# R613X.net
KiCad netlist of a schematic drawn in EAGLE
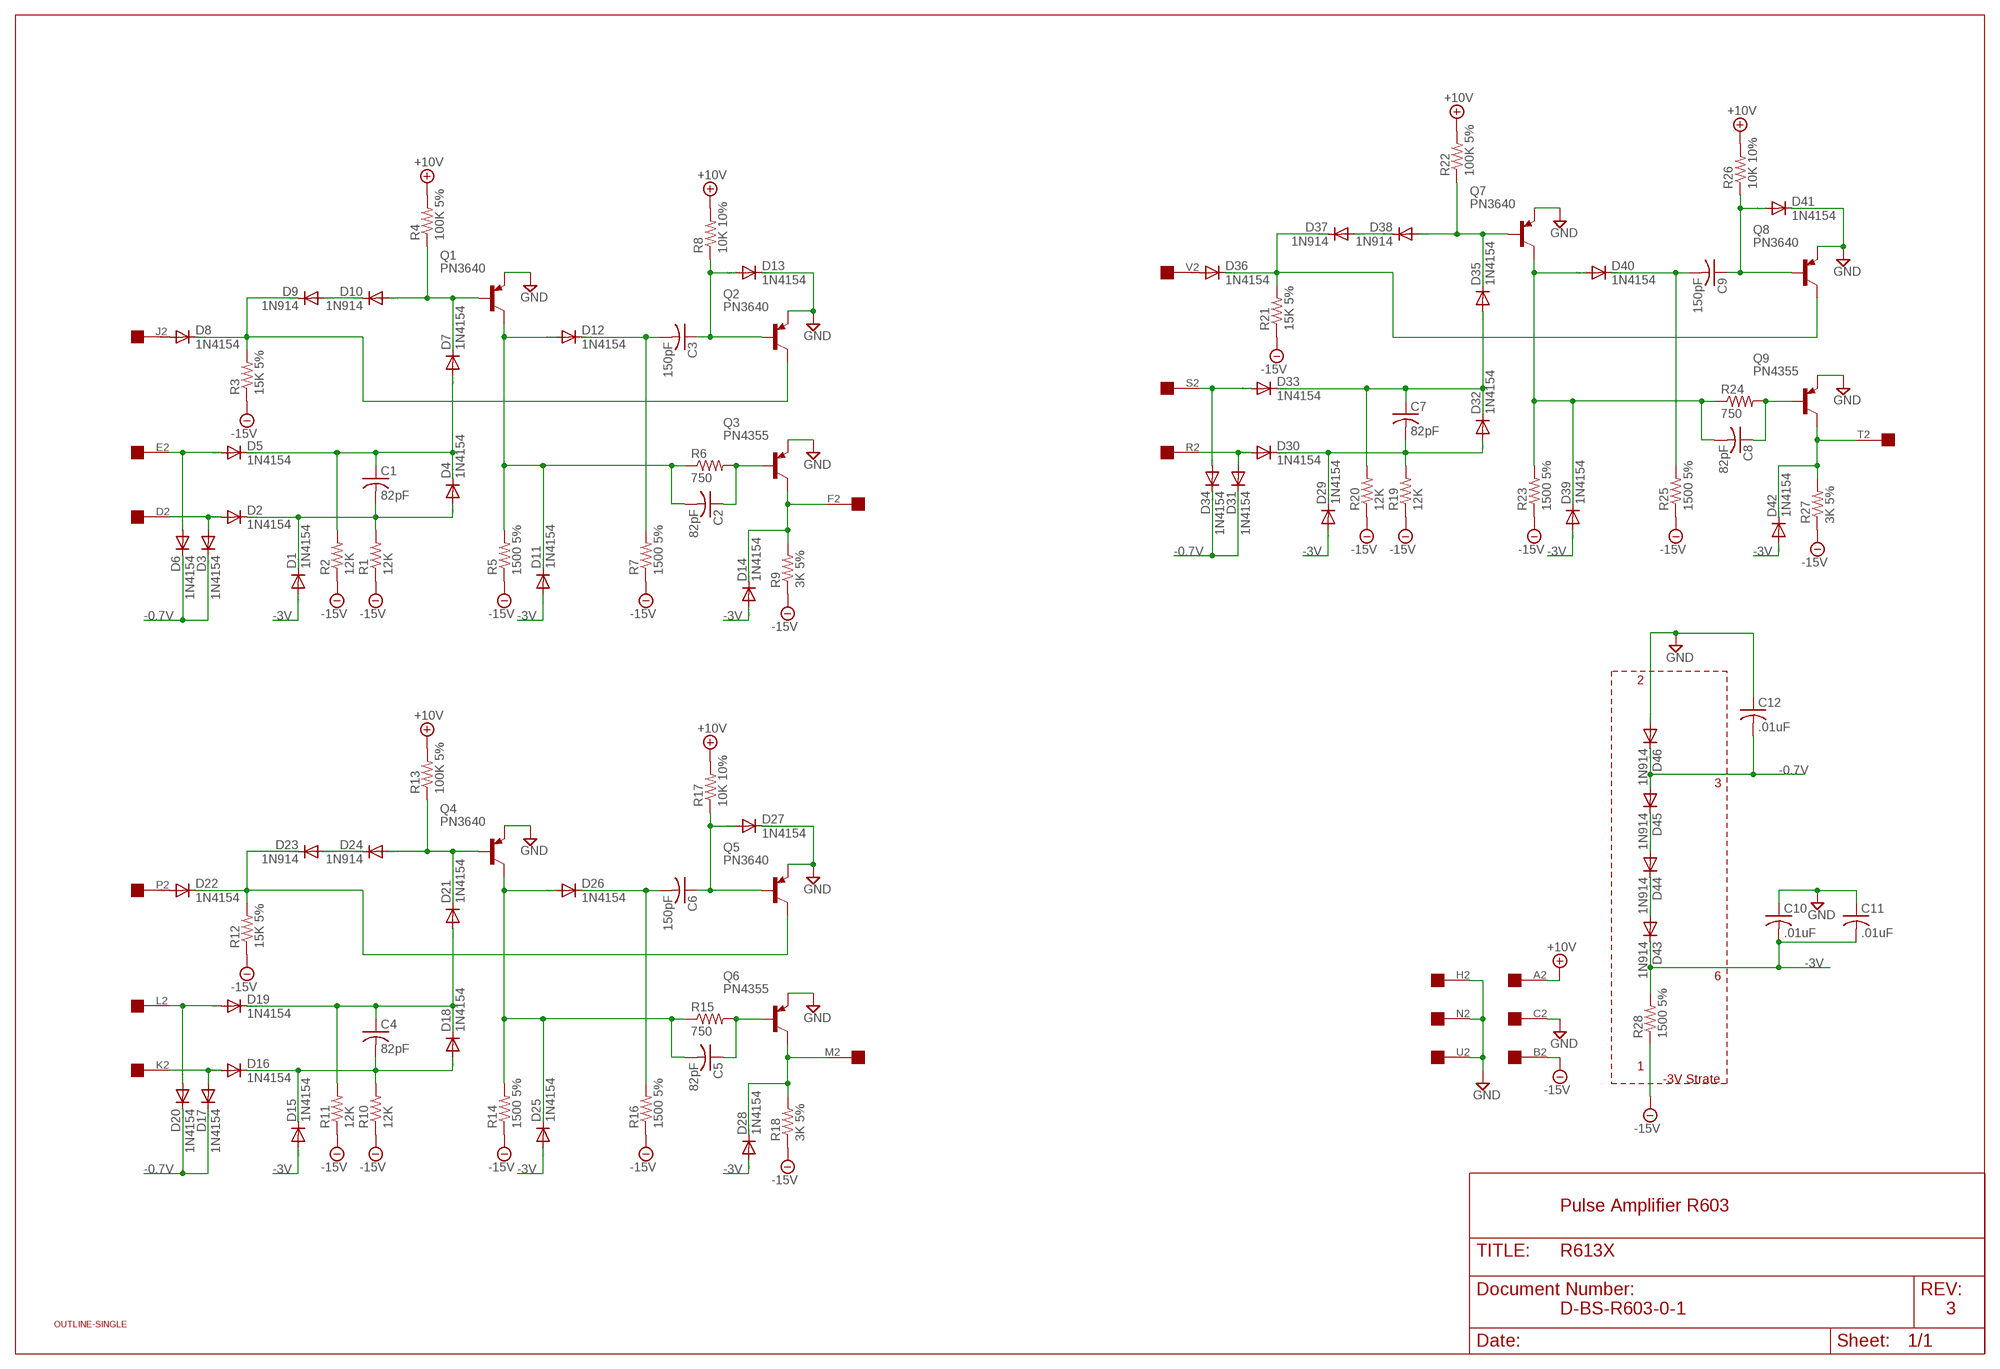
[diagram p0: schematic, sheet 1]

(export (version "E")
  (design (tool "Eeschema 10.0.6"))
  (components
    (comp (ref "C1")
      (value "82pF")
      (footprint "eagle-import:C050-025X075")
      (libsource (lib "eagle-import") (part "C-US050-025X075"))
    )
    (comp (ref "C2")
      (value "82pF")
      (footprint "eagle-import:C050-025X075")
      (libsource (lib "eagle-import") (part "C-US050-025X075"))
    )
    (comp (ref "C3")
      (value "150pF")
      (footprint "eagle-import:C050-025X075")
      (libsource (lib "eagle-import") (part "C-US050-025X075"))
    )
    (comp (ref "C4")
      (value "82pF")
      (footprint "eagle-import:C050-025X075")
      (libsource (lib "eagle-import") (part "C-US050-025X075"))
    )
    (comp (ref "C5")
      (value "82pF")
      (footprint "eagle-import:C050-025X075")
      (libsource (lib "eagle-import") (part "C-US050-025X075"))
    )
    (comp (ref "C6")
      (value "150pF")
      (footprint "eagle-import:C050-025X075")
      (libsource (lib "eagle-import") (part "C-US050-025X075"))
    )
    (comp (ref "C7")
      (value "82pF")
      (footprint "eagle-import:C050-025X075")
      (libsource (lib "eagle-import") (part "C-US050-025X075"))
    )
    (comp (ref "C8")
      (value "82pF")
      (footprint "eagle-import:C050-025X075")
      (libsource (lib "eagle-import") (part "C-US050-025X075"))
    )
    (comp (ref "C9")
      (value "150pF")
      (footprint "eagle-import:C050-025X075")
      (libsource (lib "eagle-import") (part "C-US050-025X075"))
    )
    (comp (ref "C10")
      (value ".01uF")
      (footprint "eagle-import:C050-025X075")
      (libsource (lib "eagle-import") (part "C-US050-025X075"))
    )
    (comp (ref "C11")
      (value ".01uF")
      (footprint "eagle-import:C050-025X075")
      (libsource (lib "eagle-import") (part "C-US050-025X075"))
    )
    (comp (ref "C12")
      (value ".01uF")
      (footprint "eagle-import:C050-025X075")
      (libsource (lib "eagle-import") (part "C-US050-025X075"))
    )
    (comp (ref "D1")
      (value "1N4154")
      (footprint "eagle-import:DO35-10")
      (libsource (lib "eagle-import") (part "1N4148DO35-10"))
    )
    (comp (ref "D2")
      (value "1N4154")
      (footprint "eagle-import:DO35-10")
      (libsource (lib "eagle-import") (part "1N4148DO35-10"))
    )
    (comp (ref "D3")
      (value "1N4154")
      (footprint "eagle-import:DO35-10")
      (libsource (lib "eagle-import") (part "1N4148DO35-10"))
    )
    (comp (ref "D4")
      (value "1N4154")
      (footprint "eagle-import:DO35-10")
      (libsource (lib "eagle-import") (part "1N4148DO35-10"))
    )
    (comp (ref "D5")
      (value "1N4154")
      (footprint "eagle-import:DO35-10")
      (libsource (lib "eagle-import") (part "1N4148DO35-10"))
    )
    (comp (ref "D6")
      (value "1N4154")
      (footprint "eagle-import:DO35-10")
      (libsource (lib "eagle-import") (part "1N4148DO35-10"))
    )
    (comp (ref "D7")
      (value "1N4154")
      (footprint "eagle-import:DO35-10")
      (libsource (lib "eagle-import") (part "1N4148DO35-10"))
    )
    (comp (ref "D8")
      (value "1N4154")
      (footprint "eagle-import:DO35-10")
      (libsource (lib "eagle-import") (part "1N4148DO35-10"))
    )
    (comp (ref "D9")
      (value "1N914")
      (footprint "eagle-import:DO35-10")
      (libsource (lib "eagle-import") (part "1N4148DO35-10"))
    )
    (comp (ref "D10")
      (value "1N914")
      (footprint "eagle-import:DO35-10")
      (libsource (lib "eagle-import") (part "1N4148DO35-10"))
    )
    (comp (ref "D11")
      (value "1N4154")
      (footprint "eagle-import:DO35-10")
      (libsource (lib "eagle-import") (part "1N4148DO35-10"))
    )
    (comp (ref "D12")
      (value "1N4154")
      (footprint "eagle-import:DO35-10")
      (libsource (lib "eagle-import") (part "1N4148DO35-10"))
    )
    (comp (ref "D13")
      (value "1N4154")
      (footprint "eagle-import:DO35-10")
      (libsource (lib "eagle-import") (part "1N4148DO35-10"))
    )
    (comp (ref "D14")
      (value "1N4154")
      (footprint "eagle-import:DO35-10")
      (libsource (lib "eagle-import") (part "1N4148DO35-10"))
    )
    (comp (ref "D15")
      (value "1N4154")
      (footprint "eagle-import:DO35-10")
      (libsource (lib "eagle-import") (part "1N4148DO35-10"))
    )
    (comp (ref "D16")
      (value "1N4154")
      (footprint "eagle-import:DO35-10")
      (libsource (lib "eagle-import") (part "1N4148DO35-10"))
    )
    (comp (ref "D17")
      (value "1N4154")
      (footprint "eagle-import:DO35-10")
      (libsource (lib "eagle-import") (part "1N4148DO35-10"))
    )
    (comp (ref "D18")
      (value "1N4154")
      (footprint "eagle-import:DO35-10")
      (libsource (lib "eagle-import") (part "1N4148DO35-10"))
    )
    (comp (ref "D19")
      (value "1N4154")
      (footprint "eagle-import:DO35-10")
      (libsource (lib "eagle-import") (part "1N4148DO35-10"))
    )
    (comp (ref "D20")
      (value "1N4154")
      (footprint "eagle-import:DO35-10")
      (libsource (lib "eagle-import") (part "1N4148DO35-10"))
    )
    (comp (ref "D21")
      (value "1N4154")
      (footprint "eagle-import:DO35-10")
      (libsource (lib "eagle-import") (part "1N4148DO35-10"))
    )
    (comp (ref "D22")
      (value "1N4154")
      (footprint "eagle-import:DO35-10")
      (libsource (lib "eagle-import") (part "1N4148DO35-10"))
    )
    (comp (ref "D23")
      (value "1N914")
      (footprint "eagle-import:DO35-10")
      (libsource (lib "eagle-import") (part "1N4148DO35-10"))
    )
    (comp (ref "D24")
      (value "1N914")
      (footprint "eagle-import:DO35-10")
      (libsource (lib "eagle-import") (part "1N4148DO35-10"))
    )
    (comp (ref "D25")
      (value "1N4154")
      (footprint "eagle-import:DO35-10")
      (libsource (lib "eagle-import") (part "1N4148DO35-10"))
    )
    (comp (ref "D26")
      (value "1N4154")
      (footprint "eagle-import:DO35-10")
      (libsource (lib "eagle-import") (part "1N4148DO35-10"))
    )
    (comp (ref "D27")
      (value "1N4154")
      (footprint "eagle-import:DO35-10")
      (libsource (lib "eagle-import") (part "1N4148DO35-10"))
    )
    (comp (ref "D28")
      (value "1N4154")
      (footprint "eagle-import:DO35-10")
      (libsource (lib "eagle-import") (part "1N4148DO35-10"))
    )
    (comp (ref "D29")
      (value "1N4154")
      (footprint "eagle-import:DO35-10")
      (libsource (lib "eagle-import") (part "1N4148DO35-10"))
    )
    (comp (ref "D30")
      (value "1N4154")
      (footprint "eagle-import:DO35-10")
      (libsource (lib "eagle-import") (part "1N4148DO35-10"))
    )
    (comp (ref "D31")
      (value "1N4154")
      (footprint "eagle-import:DO35-10")
      (libsource (lib "eagle-import") (part "1N4148DO35-10"))
    )
    (comp (ref "D32")
      (value "1N4154")
      (footprint "eagle-import:DO35-10")
      (libsource (lib "eagle-import") (part "1N4148DO35-10"))
    )
    (comp (ref "D33")
      (value "1N4154")
      (footprint "eagle-import:DO35-10")
      (libsource (lib "eagle-import") (part "1N4148DO35-10"))
    )
    (comp (ref "D34")
      (value "1N4154")
      (footprint "eagle-import:DO35-10")
      (libsource (lib "eagle-import") (part "1N4148DO35-10"))
    )
    (comp (ref "D35")
      (value "1N4154")
      (footprint "eagle-import:DO35-10")
      (libsource (lib "eagle-import") (part "1N4148DO35-10"))
    )
    (comp (ref "D36")
      (value "1N4154")
      (footprint "eagle-import:DO35-10")
      (libsource (lib "eagle-import") (part "1N4148DO35-10"))
    )
    (comp (ref "D37")
      (value "1N914")
      (footprint "eagle-import:DO35-10")
      (libsource (lib "eagle-import") (part "1N4148DO35-10"))
    )
    (comp (ref "D38")
      (value "1N914")
      (footprint "eagle-import:DO35-10")
      (libsource (lib "eagle-import") (part "1N4148DO35-10"))
    )
    (comp (ref "D39")
      (value "1N4154")
      (footprint "eagle-import:DO35-10")
      (libsource (lib "eagle-import") (part "1N4148DO35-10"))
    )
    (comp (ref "D40")
      (value "1N4154")
      (footprint "eagle-import:DO35-10")
      (libsource (lib "eagle-import") (part "1N4148DO35-10"))
    )
    (comp (ref "D41")
      (value "1N4154")
      (footprint "eagle-import:DO35-10")
      (libsource (lib "eagle-import") (part "1N4148DO35-10"))
    )
    (comp (ref "D42")
      (value "1N4154")
      (footprint "eagle-import:DO35-10")
      (libsource (lib "eagle-import") (part "1N4148DO35-10"))
    )
    (comp (ref "D43")
      (value "1N914")
      (footprint "eagle-import:DO35-10")
      (libsource (lib "eagle-import") (part "1N4148DO35-10"))
    )
    (comp (ref "D44")
      (value "1N914")
      (footprint "eagle-import:DO35-10")
      (libsource (lib "eagle-import") (part "1N4148DO35-10"))
    )
    (comp (ref "D45")
      (value "1N914")
      (footprint "eagle-import:DO35-10")
      (libsource (lib "eagle-import") (part "1N4148DO35-10"))
    )
    (comp (ref "D46")
      (value "1N914")
      (footprint "eagle-import:DO35-10")
      (libsource (lib "eagle-import") (part "1N4148DO35-10"))
    )
    (comp (ref "Q1")
      (value "PN3640")
      (footprint "eagle-import:TO39")
      (libsource (lib "eagle-import") (part "2N2904"))
    )
    (comp (ref "Q2")
      (value "PN3640")
      (footprint "eagle-import:TO39")
      (libsource (lib "eagle-import") (part "2N2904"))
    )
    (comp (ref "Q3")
      (value "PN4355")
      (footprint "eagle-import:TO39")
      (libsource (lib "eagle-import") (part "2N2904"))
    )
    (comp (ref "Q4")
      (value "PN3640")
      (footprint "eagle-import:TO39")
      (libsource (lib "eagle-import") (part "2N2904"))
    )
    (comp (ref "Q5")
      (value "PN3640")
      (footprint "eagle-import:TO39")
      (libsource (lib "eagle-import") (part "2N2904"))
    )
    (comp (ref "Q6")
      (value "PN4355")
      (footprint "eagle-import:TO39")
      (libsource (lib "eagle-import") (part "2N2904"))
    )
    (comp (ref "Q7")
      (value "PN3640")
      (footprint "eagle-import:TO39")
      (libsource (lib "eagle-import") (part "2N2904"))
    )
    (comp (ref "Q8")
      (value "PN3640")
      (footprint "eagle-import:TO39")
      (libsource (lib "eagle-import") (part "2N2904"))
    )
    (comp (ref "Q9")
      (value "PN4355")
      (footprint "eagle-import:TO39")
      (libsource (lib "eagle-import") (part "2N2904"))
    )
    (comp (ref "R1")
      (value "12K")
      (footprint "eagle-import:0207_10")
      (libsource (lib "eagle-import") (part "R-US_0207/10"))
    )
    (comp (ref "R2")
      (value "12K")
      (footprint "eagle-import:0207_10")
      (libsource (lib "eagle-import") (part "R-US_0207/10"))
    )
    (comp (ref "R3")
      (value "15K 5%")
      (footprint "eagle-import:0207_10")
      (libsource (lib "eagle-import") (part "R-US_0207/10"))
    )
    (comp (ref "R4")
      (value "100K 5%")
      (footprint "eagle-import:0207_10")
      (libsource (lib "eagle-import") (part "R-US_0207/10"))
    )
    (comp (ref "R5")
      (value "1500 5%")
      (footprint "eagle-import:0207_10")
      (libsource (lib "eagle-import") (part "R-US_0207/10"))
    )
    (comp (ref "R6")
      (value "750")
      (footprint "eagle-import:0207_10")
      (libsource (lib "eagle-import") (part "R-US_0207/10"))
    )
    (comp (ref "R7")
      (value "1500 5%")
      (footprint "eagle-import:0207_10")
      (libsource (lib "eagle-import") (part "R-US_0207/10"))
    )
    (comp (ref "R8")
      (value "10K 10%")
      (footprint "eagle-import:0207_10")
      (libsource (lib "eagle-import") (part "R-US_0207/10"))
    )
    (comp (ref "R9")
      (value "3K 5%")
      (footprint "eagle-import:0207_10")
      (libsource (lib "eagle-import") (part "R-US_0207/10"))
    )
    (comp (ref "R10")
      (value "12K")
      (footprint "eagle-import:0207_10")
      (libsource (lib "eagle-import") (part "R-US_0207/10"))
    )
    (comp (ref "R11")
      (value "12K")
      (footprint "eagle-import:0207_10")
      (libsource (lib "eagle-import") (part "R-US_0207/10"))
    )
    (comp (ref "R12")
      (value "15K 5%")
      (footprint "eagle-import:0207_10")
      (libsource (lib "eagle-import") (part "R-US_0207/10"))
    )
    (comp (ref "R13")
      (value "100K 5%")
      (footprint "eagle-import:0207_10")
      (libsource (lib "eagle-import") (part "R-US_0207/10"))
    )
    (comp (ref "R14")
      (value "1500 5%")
      (footprint "eagle-import:0207_10")
      (libsource (lib "eagle-import") (part "R-US_0207/10"))
    )
    (comp (ref "R15")
      (value "750")
      (footprint "eagle-import:0207_10")
      (libsource (lib "eagle-import") (part "R-US_0207/10"))
    )
    (comp (ref "R16")
      (value "1500 5%")
      (footprint "eagle-import:0207_10")
      (libsource (lib "eagle-import") (part "R-US_0207/10"))
    )
    (comp (ref "R17")
      (value "10K 10%")
      (footprint "eagle-import:0207_10")
      (libsource (lib "eagle-import") (part "R-US_0207/10"))
    )
    (comp (ref "R18")
      (value "3K 5%")
      (footprint "eagle-import:0207_10")
      (libsource (lib "eagle-import") (part "R-US_0207/10"))
    )
    (comp (ref "R19")
      (value "12K")
      (footprint "eagle-import:0207_10")
      (libsource (lib "eagle-import") (part "R-US_0207/10"))
    )
    (comp (ref "R20")
      (value "12K")
      (footprint "eagle-import:0207_10")
      (libsource (lib "eagle-import") (part "R-US_0207/10"))
    )
    (comp (ref "R21")
      (value "15K 5%")
      (footprint "eagle-import:0207_10")
      (libsource (lib "eagle-import") (part "R-US_0207/10"))
    )
    (comp (ref "R22")
      (value "100K 5%")
      (footprint "eagle-import:0207_10")
      (libsource (lib "eagle-import") (part "R-US_0207/10"))
    )
    (comp (ref "R23")
      (value "1500 5%")
      (footprint "eagle-import:0207_10")
      (libsource (lib "eagle-import") (part "R-US_0207/10"))
    )
    (comp (ref "R24")
      (value "750")
      (footprint "eagle-import:0207_10")
      (libsource (lib "eagle-import") (part "R-US_0207/10"))
    )
    (comp (ref "R25")
      (value "1500 5%")
      (footprint "eagle-import:0207_10")
      (libsource (lib "eagle-import") (part "R-US_0207/10"))
    )
    (comp (ref "R26")
      (value "10K 10%")
      (footprint "eagle-import:0207_10")
      (libsource (lib "eagle-import") (part "R-US_0207/10"))
    )
    (comp (ref "R27")
      (value "3K 5%")
      (footprint "eagle-import:0207_10")
      (libsource (lib "eagle-import") (part "R-US_0207/10"))
    )
    (comp (ref "R28")
      (value "1500 5%")
      (footprint "eagle-import:0207_10")
      (libsource (lib "eagle-import") (part "R-US_0207/10"))
    )
    (comp (ref "U$1")
      (value "OUTLINE-SINGLE")
      (footprint "eagle-import:SINGLE")
      (libsource (lib "eagle-import") (part "OUTLINE-SINGLE"))
    )
    (comp (ref "U$2")
      (value "EDGE-1")
      (footprint "eagle-import:EDGE-CON1")
      (libsource (lib "eagle-import") (part "EDGE-1"))
    )
  )
  (nets
    (net (code "1") (name "+10V") (class "Default")
      (node (ref "R13") (pin "2") (pinfunction "2_2") (pintype "passive"))
      (node (ref "R17") (pin "2") (pinfunction "2_2") (pintype "passive"))
      (node (ref "R22") (pin "2") (pinfunction "2_2") (pintype "passive"))
      (node (ref "R26") (pin "2") (pinfunction "2_2") (pintype "passive"))
      (node (ref "R4") (pin "2") (pinfunction "2_2") (pintype "passive"))
      (node (ref "R8") (pin "2") (pinfunction "2_2") (pintype "passive"))
      (node (ref "U$2") (pin "A2") (pinfunction "1_A2") (pintype "bidirectional"))
    )
    (net (code "2") (name "-15V") (class "Default")
      (node (ref "R1") (pin "1") (pinfunction "1_1") (pintype "passive"))
      (node (ref "R10") (pin "1") (pinfunction "1_1") (pintype "passive"))
      (node (ref "R11") (pin "1") (pinfunction "1_1") (pintype "passive"))
      (node (ref "R12") (pin "1") (pinfunction "1_1") (pintype "passive"))
      (node (ref "R14") (pin "1") (pinfunction "1_1") (pintype "passive"))
      (node (ref "R16") (pin "1") (pinfunction "1_1") (pintype "passive"))
      (node (ref "R18") (pin "1") (pinfunction "1_1") (pintype "passive"))
      (node (ref "R19") (pin "1") (pinfunction "1_1") (pintype "passive"))
      (node (ref "R2") (pin "1") (pinfunction "1_1") (pintype "passive"))
      (node (ref "R20") (pin "1") (pinfunction "1_1") (pintype "passive"))
      (node (ref "R21") (pin "1") (pinfunction "1_1") (pintype "passive"))
      (node (ref "R23") (pin "1") (pinfunction "1_1") (pintype "passive"))
      (node (ref "R25") (pin "1") (pinfunction "1_1") (pintype "passive"))
      (node (ref "R27") (pin "1") (pinfunction "1_1") (pintype "passive"))
      (node (ref "R28") (pin "1") (pinfunction "1_1") (pintype "passive"))
      (node (ref "R3") (pin "1") (pinfunction "1_1") (pintype "passive"))
      (node (ref "R5") (pin "1") (pinfunction "1_1") (pintype "passive"))
      (node (ref "R7") (pin "1") (pinfunction "1_1") (pintype "passive"))
      (node (ref "R9") (pin "1") (pinfunction "1_1") (pintype "passive"))
      (node (ref "U$2") (pin "B2") (pinfunction "1_B2") (pintype "bidirectional"))
    )
    (net (code "3") (name "/-0.7V") (class "Default")
      (node (ref "C12") (pin "2") (pinfunction "2_2") (pintype "passive"))
      (node (ref "D17") (pin "C") (pinfunction "C_C") (pintype "passive"))
      (node (ref "D20") (pin "C") (pinfunction "C_C") (pintype "passive"))
      (node (ref "D3") (pin "C") (pinfunction "C_C") (pintype "passive"))
      (node (ref "D31") (pin "C") (pinfunction "C_C") (pintype "passive"))
      (node (ref "D34") (pin "C") (pinfunction "C_C") (pintype "passive"))
      (node (ref "D45") (pin "A") (pinfunction "A_A") (pintype "passive"))
      (node (ref "D46") (pin "C") (pinfunction "C_C") (pintype "passive"))
      (node (ref "D6") (pin "C") (pinfunction "C_C") (pintype "passive"))
    )
    (net (code "4") (name "/-3V") (class "Default")
      (node (ref "C10") (pin "2") (pinfunction "2_2") (pintype "passive"))
      (node (ref "C11") (pin "2") (pinfunction "2_2") (pintype "passive"))
      (node (ref "D1") (pin "A") (pinfunction "A_A") (pintype "passive"))
      (node (ref "D11") (pin "A") (pinfunction "A_A") (pintype "passive"))
      (node (ref "D14") (pin "A") (pinfunction "A_A") (pintype "passive"))
      (node (ref "D15") (pin "A") (pinfunction "A_A") (pintype "passive"))
      (node (ref "D25") (pin "A") (pinfunction "A_A") (pintype "passive"))
      (node (ref "D28") (pin "A") (pinfunction "A_A") (pintype "passive"))
      (node (ref "D29") (pin "A") (pinfunction "A_A") (pintype "passive"))
      (node (ref "D39") (pin "A") (pinfunction "A_A") (pintype "passive"))
      (node (ref "D42") (pin "A") (pinfunction "A_A") (pintype "passive"))
      (node (ref "D43") (pin "C") (pinfunction "C_C") (pintype "passive"))
      (node (ref "R28") (pin "2") (pinfunction "2_2") (pintype "passive"))
    )
    (net (code "5") (name "GND") (class "Default")
      (node (ref "C10") (pin "1") (pinfunction "1_1") (pintype "passive"))
      (node (ref "C11") (pin "1") (pinfunction "1_1") (pintype "passive"))
      (node (ref "C12") (pin "1") (pinfunction "1_1") (pintype "passive"))
      (node (ref "D13") (pin "C") (pinfunction "C_C") (pintype "passive"))
      (node (ref "D27") (pin "C") (pinfunction "C_C") (pintype "passive"))
      (node (ref "D41") (pin "C") (pinfunction "C_C") (pintype "passive"))
      (node (ref "D46") (pin "A") (pinfunction "A_A") (pintype "passive"))
      (node (ref "Q1") (pin "1") (pinfunction "E_1") (pintype "passive"))
      (node (ref "Q2") (pin "1") (pinfunction "E_1") (pintype "passive"))
      (node (ref "Q3") (pin "1") (pinfunction "E_1") (pintype "passive"))
      (node (ref "Q4") (pin "1") (pinfunction "E_1") (pintype "passive"))
      (node (ref "Q5") (pin "1") (pinfunction "E_1") (pintype "passive"))
      (node (ref "Q6") (pin "1") (pinfunction "E_1") (pintype "passive"))
      (node (ref "Q7") (pin "1") (pinfunction "E_1") (pintype "passive"))
      (node (ref "Q8") (pin "1") (pinfunction "E_1") (pintype "passive"))
      (node (ref "Q9") (pin "1") (pinfunction "E_1") (pintype "passive"))
      (node (ref "U$2") (pin "C2") (pinfunction "1_C2") (pintype "bidirectional"))
      (node (ref "U$2") (pin "H2") (pinfunction "1_H2") (pintype "bidirectional"))
      (node (ref "U$2") (pin "N2") (pinfunction "1_N2") (pintype "bidirectional"))
      (node (ref "U$2") (pin "U2") (pinfunction "1_U2") (pintype "bidirectional"))
    )
    (net (code "6") (name "Net-(C1-Pad1)") (class "Default")
      (node (ref "C1") (pin "1") (pinfunction "1_1") (pintype "passive"))
      (node (ref "D4") (pin "C") (pinfunction "C_C") (pintype "passive"))
      (node (ref "D5") (pin "C") (pinfunction "C_C") (pintype "passive"))
      (node (ref "D7") (pin "A") (pinfunction "A_A") (pintype "passive"))
      (node (ref "R2") (pin "2") (pinfunction "2_2") (pintype "passive"))
    )
    (net (code "7") (name "Net-(C1-Pad2)") (class "Default")
      (node (ref "C1") (pin "2") (pinfunction "2_2") (pintype "passive"))
      (node (ref "D1") (pin "C") (pinfunction "C_C") (pintype "passive"))
      (node (ref "D2") (pin "C") (pinfunction "C_C") (pintype "passive"))
      (node (ref "D4") (pin "A") (pinfunction "A_A") (pintype "passive"))
      (node (ref "R1") (pin "2") (pinfunction "2_2") (pintype "passive"))
    )
    (net (code "8") (name "Net-(C3-Pad2)") (class "Default")
      (node (ref "C3") (pin "2") (pinfunction "2_2") (pintype "passive"))
      (node (ref "D12") (pin "C") (pinfunction "C_C") (pintype "passive"))
      (node (ref "R7") (pin "2") (pinfunction "2_2") (pintype "passive"))
    )
    (net (code "9") (name "Net-(C4-Pad1)") (class "Default")
      (node (ref "C4") (pin "1") (pinfunction "1_1") (pintype "passive"))
      (node (ref "D18") (pin "C") (pinfunction "C_C") (pintype "passive"))
      (node (ref "D19") (pin "C") (pinfunction "C_C") (pintype "passive"))
      (node (ref "D21") (pin "A") (pinfunction "A_A") (pintype "passive"))
      (node (ref "R11") (pin "2") (pinfunction "2_2") (pintype "passive"))
    )
    (net (code "10") (name "Net-(C4-Pad2)") (class "Default")
      (node (ref "C4") (pin "2") (pinfunction "2_2") (pintype "passive"))
      (node (ref "D15") (pin "C") (pinfunction "C_C") (pintype "passive"))
      (node (ref "D16") (pin "C") (pinfunction "C_C") (pintype "passive"))
      (node (ref "D18") (pin "A") (pinfunction "A_A") (pintype "passive"))
      (node (ref "R10") (pin "2") (pinfunction "2_2") (pintype "passive"))
    )
    (net (code "11") (name "Net-(C6-Pad2)") (class "Default")
      (node (ref "C6") (pin "2") (pinfunction "2_2") (pintype "passive"))
      (node (ref "D26") (pin "C") (pinfunction "C_C") (pintype "passive"))
      (node (ref "R16") (pin "2") (pinfunction "2_2") (pintype "passive"))
    )
    (net (code "12") (name "Net-(C7-Pad1)") (class "Default")
      (node (ref "C7") (pin "1") (pinfunction "1_1") (pintype "passive"))
      (node (ref "D32") (pin "C") (pinfunction "C_C") (pintype "passive"))
      (node (ref "D33") (pin "C") (pinfunction "C_C") (pintype "passive"))
      (node (ref "D35") (pin "A") (pinfunction "A_A") (pintype "passive"))
      (node (ref "R20") (pin "2") (pinfunction "2_2") (pintype "passive"))
    )
    (net (code "13") (name "Net-(C7-Pad2)") (class "Default")
      (node (ref "C7") (pin "2") (pinfunction "2_2") (pintype "passive"))
      (node (ref "D29") (pin "C") (pinfunction "C_C") (pintype "passive"))
      (node (ref "D30") (pin "C") (pinfunction "C_C") (pintype "passive"))
      (node (ref "D32") (pin "A") (pinfunction "A_A") (pintype "passive"))
      (node (ref "R19") (pin "2") (pinfunction "2_2") (pintype "passive"))
    )
    (net (code "14") (name "Net-(C9-Pad2)") (class "Default")
      (node (ref "C9") (pin "2") (pinfunction "2_2") (pintype "passive"))
      (node (ref "D40") (pin "C") (pinfunction "C_C") (pintype "passive"))
      (node (ref "R25") (pin "2") (pinfunction "2_2") (pintype "passive"))
    )
    (net (code "15") (name "Net-(D10-PadC)") (class "Default")
      (node (ref "D10") (pin "C") (pinfunction "C_C") (pintype "passive"))
      (node (ref "D9") (pin "A") (pinfunction "A_A") (pintype "passive"))
    )
    (net (code "16") (name "Net-(D23-PadA)") (class "Default")
      (node (ref "D23") (pin "A") (pinfunction "A_A") (pintype "passive"))
      (node (ref "D24") (pin "C") (pinfunction "C_C") (pintype "passive"))
    )
    (net (code "17") (name "Net-(D37-PadA)") (class "Default")
      (node (ref "D37") (pin "A") (pinfunction "A_A") (pintype "passive"))
      (node (ref "D38") (pin "C") (pinfunction "C_C") (pintype "passive"))
    )
    (net (code "18") (name "Net-(D43-PadA)") (class "Default")
      (node (ref "D43") (pin "A") (pinfunction "A_A") (pintype "passive"))
      (node (ref "D44") (pin "C") (pinfunction "C_C") (pintype "passive"))
    )
    (net (code "19") (name "Net-(D44-PadA)") (class "Default")
      (node (ref "D44") (pin "A") (pinfunction "A_A") (pintype "passive"))
      (node (ref "D45") (pin "C") (pinfunction "C_C") (pintype "passive"))
    )
    (net (code "20") (name "Net-(Q1-B)") (class "Default")
      (node (ref "D10") (pin "A") (pinfunction "A_A") (pintype "passive"))
      (node (ref "D7") (pin "C") (pinfunction "C_C") (pintype "passive"))
      (node (ref "Q1") (pin "2") (pinfunction "B_2") (pintype "passive"))
      (node (ref "R4") (pin "1") (pinfunction "1_1") (pintype "passive"))
    )
    (net (code "21") (name "Net-(Q1-C)") (class "Default")
      (node (ref "C2") (pin "2") (pinfunction "2_2") (pintype "passive"))
      (node (ref "D11") (pin "C") (pinfunction "C_C") (pintype "passive"))
      (node (ref "D12") (pin "A") (pinfunction "A_A") (pintype "passive"))
      (node (ref "Q1") (pin "3") (pinfunction "C_3") (pintype "passive"))
      (node (ref "R5") (pin "2") (pinfunction "2_2") (pintype "passive"))
      (node (ref "R6") (pin "1") (pinfunction "1_1") (pintype "passive"))
    )
    (net (code "22") (name "Net-(Q2-B)") (class "Default")
      (node (ref "C3") (pin "1") (pinfunction "1_1") (pintype "passive"))
      (node (ref "D13") (pin "A") (pinfunction "A_A") (pintype "passive"))
      (node (ref "Q2") (pin "2") (pinfunction "B_2") (pintype "passive"))
      (node (ref "R8") (pin "1") (pinfunction "1_1") (pintype "passive"))
    )
    (net (code "23") (name "Net-(Q2-C)") (class "Default")
      (node (ref "D8") (pin "C") (pinfunction "C_C") (pintype "passive"))
      (node (ref "D9") (pin "C") (pinfunction "C_C") (pintype "passive"))
      (node (ref "Q2") (pin "3") (pinfunction "C_3") (pintype "passive"))
      (node (ref "R3") (pin "2") (pinfunction "2_2") (pintype "passive"))
    )
    (net (code "24") (name "Net-(Q3-B)") (class "Default")
      (node (ref "C2") (pin "1") (pinfunction "1_1") (pintype "passive"))
      (node (ref "Q3") (pin "2") (pinfunction "B_2") (pintype "passive"))
      (node (ref "R6") (pin "2") (pinfunction "2_2") (pintype "passive"))
    )
    (net (code "25") (name "Net-(Q3-C)") (class "Default")
      (node (ref "D14") (pin "C") (pinfunction "C_C") (pintype "passive"))
      (node (ref "Q3") (pin "3") (pinfunction "C_3") (pintype "passive"))
      (node (ref "R9") (pin "2") (pinfunction "2_2") (pintype "passive"))
      (node (ref "U$2") (pin "F2") (pinfunction "1_F2") (pintype "bidirectional"))
    )
    (net (code "26") (name "Net-(Q4-B)") (class "Default")
      (node (ref "D21") (pin "C") (pinfunction "C_C") (pintype "passive"))
      (node (ref "D24") (pin "A") (pinfunction "A_A") (pintype "passive"))
      (node (ref "Q4") (pin "2") (pinfunction "B_2") (pintype "passive"))
      (node (ref "R13") (pin "1") (pinfunction "1_1") (pintype "passive"))
    )
    (net (code "27") (name "Net-(Q4-C)") (class "Default")
      (node (ref "C5") (pin "2") (pinfunction "2_2") (pintype "passive"))
      (node (ref "D25") (pin "C") (pinfunction "C_C") (pintype "passive"))
      (node (ref "D26") (pin "A") (pinfunction "A_A") (pintype "passive"))
      (node (ref "Q4") (pin "3") (pinfunction "C_3") (pintype "passive"))
      (node (ref "R14") (pin "2") (pinfunction "2_2") (pintype "passive"))
      (node (ref "R15") (pin "1") (pinfunction "1_1") (pintype "passive"))
    )
    (net (code "28") (name "Net-(Q5-B)") (class "Default")
      (node (ref "C6") (pin "1") (pinfunction "1_1") (pintype "passive"))
      (node (ref "D27") (pin "A") (pinfunction "A_A") (pintype "passive"))
      (node (ref "Q5") (pin "2") (pinfunction "B_2") (pintype "passive"))
      (node (ref "R17") (pin "1") (pinfunction "1_1") (pintype "passive"))
    )
    (net (code "29") (name "Net-(Q5-C)") (class "Default")
      (node (ref "D22") (pin "C") (pinfunction "C_C") (pintype "passive"))
      (node (ref "D23") (pin "C") (pinfunction "C_C") (pintype "passive"))
      (node (ref "Q5") (pin "3") (pinfunction "C_3") (pintype "passive"))
      (node (ref "R12") (pin "2") (pinfunction "2_2") (pintype "passive"))
    )
    (net (code "30") (name "Net-(Q6-B)") (class "Default")
      (node (ref "C5") (pin "1") (pinfunction "1_1") (pintype "passive"))
      (node (ref "Q6") (pin "2") (pinfunction "B_2") (pintype "passive"))
      (node (ref "R15") (pin "2") (pinfunction "2_2") (pintype "passive"))
    )
    (net (code "31") (name "Net-(Q6-C)") (class "Default")
      (node (ref "D28") (pin "C") (pinfunction "C_C") (pintype "passive"))
      (node (ref "Q6") (pin "3") (pinfunction "C_3") (pintype "passive"))
      (node (ref "R18") (pin "2") (pinfunction "2_2") (pintype "passive"))
      (node (ref "U$2") (pin "M2") (pinfunction "1_M2") (pintype "bidirectional"))
    )
    (net (code "32") (name "Net-(Q7-B)") (class "Default")
      (node (ref "D35") (pin "C") (pinfunction "C_C") (pintype "passive"))
      (node (ref "D38") (pin "A") (pinfunction "A_A") (pintype "passive"))
      (node (ref "Q7") (pin "2") (pinfunction "B_2") (pintype "passive"))
      (node (ref "R22") (pin "1") (pinfunction "1_1") (pintype "passive"))
    )
    (net (code "33") (name "Net-(Q7-C)") (class "Default")
      (node (ref "C8") (pin "2") (pinfunction "2_2") (pintype "passive"))
      (node (ref "D39") (pin "C") (pinfunction "C_C") (pintype "passive"))
      (node (ref "D40") (pin "A") (pinfunction "A_A") (pintype "passive"))
      (node (ref "Q7") (pin "3") (pinfunction "C_3") (pintype "passive"))
      (node (ref "R23") (pin "2") (pinfunction "2_2") (pintype "passive"))
      (node (ref "R24") (pin "1") (pinfunction "1_1") (pintype "passive"))
    )
    (net (code "34") (name "Net-(Q8-B)") (class "Default")
      (node (ref "C9") (pin "1") (pinfunction "1_1") (pintype "passive"))
      (node (ref "D41") (pin "A") (pinfunction "A_A") (pintype "passive"))
      (node (ref "Q8") (pin "2") (pinfunction "B_2") (pintype "passive"))
      (node (ref "R26") (pin "1") (pinfunction "1_1") (pintype "passive"))
    )
    (net (code "35") (name "Net-(Q8-C)") (class "Default")
      (node (ref "D36") (pin "C") (pinfunction "C_C") (pintype "passive"))
      (node (ref "D37") (pin "C") (pinfunction "C_C") (pintype "passive"))
      (node (ref "Q8") (pin "3") (pinfunction "C_3") (pintype "passive"))
      (node (ref "R21") (pin "2") (pinfunction "2_2") (pintype "passive"))
    )
    (net (code "36") (name "Net-(Q9-B)") (class "Default")
      (node (ref "C8") (pin "1") (pinfunction "1_1") (pintype "passive"))
      (node (ref "Q9") (pin "2") (pinfunction "B_2") (pintype "passive"))
      (node (ref "R24") (pin "2") (pinfunction "2_2") (pintype "passive"))
    )
    (net (code "37") (name "Net-(Q9-C)") (class "Default")
      (node (ref "D42") (pin "C") (pinfunction "C_C") (pintype "passive"))
      (node (ref "Q9") (pin "3") (pinfunction "C_3") (pintype "passive"))
      (node (ref "R27") (pin "2") (pinfunction "2_2") (pintype "passive"))
      (node (ref "U$2") (pin "T2") (pinfunction "1_T2") (pintype "bidirectional"))
    )
    (net (code "38") (name "Net-(U$2D-1)") (class "Default")
      (node (ref "D2") (pin "A") (pinfunction "A_A") (pintype "passive"))
      (node (ref "D3") (pin "A") (pinfunction "A_A") (pintype "passive"))
      (node (ref "U$2") (pin "D2") (pinfunction "1_D2") (pintype "bidirectional"))
    )
    (net (code "39") (name "Net-(U$2E-1)") (class "Default")
      (node (ref "D5") (pin "A") (pinfunction "A_A") (pintype "passive"))
      (node (ref "D6") (pin "A") (pinfunction "A_A") (pintype "passive"))
      (node (ref "U$2") (pin "E2") (pinfunction "1_E2") (pintype "bidirectional"))
    )
    (net (code "40") (name "Net-(U$2H-1)") (class "Default")
      (node (ref "D8") (pin "A") (pinfunction "A_A") (pintype "passive"))
      (node (ref "U$2") (pin "J2") (pinfunction "1_J2") (pintype "bidirectional"))
    )
    (net (code "41") (name "Net-(U$2I-1)") (class "Default")
      (node (ref "D16") (pin "A") (pinfunction "A_A") (pintype "passive"))
      (node (ref "D17") (pin "A") (pinfunction "A_A") (pintype "passive"))
      (node (ref "U$2") (pin "K2") (pinfunction "1_K2") (pintype "bidirectional"))
    )
    (net (code "42") (name "Net-(U$2J-1)") (class "Default")
      (node (ref "D19") (pin "A") (pinfunction "A_A") (pintype "passive"))
      (node (ref "D20") (pin "A") (pinfunction "A_A") (pintype "passive"))
      (node (ref "U$2") (pin "L2") (pinfunction "1_L2") (pintype "bidirectional"))
    )
    (net (code "43") (name "Net-(U$2M-1)") (class "Default")
      (node (ref "D22") (pin "A") (pinfunction "A_A") (pintype "passive"))
      (node (ref "U$2") (pin "P2") (pinfunction "1_P2") (pintype "bidirectional"))
    )
    (net (code "44") (name "Net-(U$2N-1)") (class "Default")
      (node (ref "D30") (pin "A") (pinfunction "A_A") (pintype "passive"))
      (node (ref "D31") (pin "A") (pinfunction "A_A") (pintype "passive"))
      (node (ref "U$2") (pin "R2") (pinfunction "1_R2") (pintype "bidirectional"))
    )
    (net (code "45") (name "Net-(U$2O-1)") (class "Default")
      (node (ref "D33") (pin "A") (pinfunction "A_A") (pintype "passive"))
      (node (ref "D34") (pin "A") (pinfunction "A_A") (pintype "passive"))
      (node (ref "U$2") (pin "S2") (pinfunction "1_S2") (pintype "bidirectional"))
    )
    (net (code "46") (name "Net-(U$2R-1)") (class "Default")
      (node (ref "D36") (pin "A") (pinfunction "A_A") (pintype "passive"))
      (node (ref "U$2") (pin "V2") (pinfunction "1_V2") (pintype "bidirectional"))
    )
  )
)
